# logic-noise-filters-and-drums.net
KiCad netlist of a schematic drawn in EAGLE
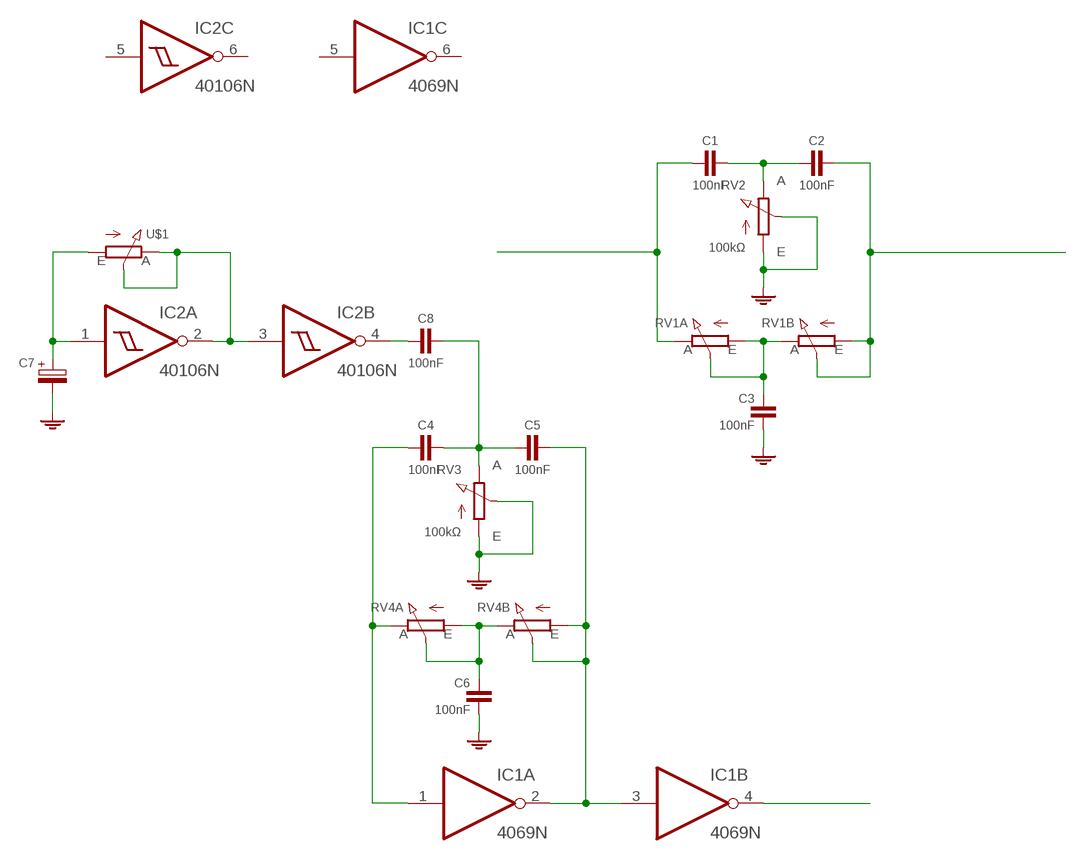
[diagram p0: schematic, sheet 1]

(export (version "E")
  (design (tool "Eeschema 10.0.6"))
  (components
    (comp (ref "C1")
      (value "100nF")
      (footprint "eagle-import:C075-020X044")
      (libsource (lib "eagle-import") (part "C-H075-020X044"))
    )
    (comp (ref "C2")
      (value "100nF")
      (footprint "eagle-import:C075-020X044")
      (libsource (lib "eagle-import") (part "C-H075-020X044"))
    )
    (comp (ref "C3")
      (value "100nF")
      (footprint "eagle-import:C075-020X044")
      (libsource (lib "eagle-import") (part "C075-020X044"))
    )
    (comp (ref "C4")
      (value "100nF")
      (footprint "eagle-import:C075-020X044")
      (libsource (lib "eagle-import") (part "C-H075-020X044"))
    )
    (comp (ref "C5")
      (value "100nF")
      (footprint "eagle-import:C075-020X044")
      (libsource (lib "eagle-import") (part "C-H075-020X044"))
    )
    (comp (ref "C6")
      (value "100nF")
      (footprint "eagle-import:C075-020X044")
      (libsource (lib "eagle-import") (part "C075-020X044"))
    )
    (comp (ref "C7")
      (value "CPOLE2,5-5/V")
      (footprint "eagle-import:E2,5-5_V")
      (libsource (lib "eagle-import") (part "CPOLE2,5-5/V"))
    )
    (comp (ref "C8")
      (value "100nF")
      (footprint "eagle-import:C075-020X044")
      (libsource (lib "eagle-import") (part "C-H075-020X044"))
    )
    (comp (ref "IC1")
      (value "4069N")
      (footprint "eagle-import:DIL14")
      (libsource (lib "eagle-import") (part "4069N"))
    )
    (comp (ref "IC2")
      (value "40106N")
      (footprint "eagle-import:DIL14")
      (libsource (lib "eagle-import") (part "40106N"))
    )
    (comp (ref "RV1")
      (value "POT-STEREO")
      (footprint "eagle-import:POT-STEREO-2X3")
      (libsource (lib "eagle-import") (part "POT-STEREO"))
    )
    (comp (ref "RV2")
      (value "100kΩ")
      (footprint "eagle-import:POT")
      (libsource (lib "eagle-import") (part "POT"))
    )
    (comp (ref "RV3")
      (value "100kΩ")
      (footprint "eagle-import:POT")
      (libsource (lib "eagle-import") (part "POT"))
    )
    (comp (ref "RV4")
      (value "POT-STEREO")
      (footprint "eagle-import:POT-STEREO-2X3")
      (libsource (lib "eagle-import") (part "POT-STEREO"))
    )
    (comp (ref "U$1")
      (value "POT-H")
      (footprint "eagle-import:POT")
      (libsource (lib "eagle-import") (part "POT-H"))
    )
  )
  (nets
    (net (code "1") (name "GND") (class "Default")
      (node (ref "C3") (pin "2") (pinfunction "2_2") (pintype "passive"))
      (node (ref "C6") (pin "2") (pinfunction "2_2") (pintype "passive"))
      (node (ref "C7") (pin "-") (pinfunction "-_-") (pintype "passive"))
      (node (ref "RV2") (pin "A") (pinfunction "A_A") (pintype "passive"))
      (node (ref "RV2") (pin "S") (pinfunction "S_S") (pintype "passive"))
      (node (ref "RV3") (pin "A") (pinfunction "A_A") (pintype "passive"))
      (node (ref "RV3") (pin "S") (pinfunction "S_S") (pintype "passive"))
    )
    (net (code "2") (name "Net-(C1-Pad2)") (class "Default")
      (node (ref "C1") (pin "2") (pinfunction "2_2") (pintype "passive"))
      (node (ref "C2") (pin "1") (pinfunction "1_1") (pintype "passive"))
      (node (ref "RV2") (pin "E") (pinfunction "E_E") (pintype "passive"))
    )
    (net (code "3") (name "Net-(C4-Pad2)") (class "Default")
      (node (ref "C4") (pin "2") (pinfunction "2_2") (pintype "passive"))
      (node (ref "C5") (pin "1") (pinfunction "1_1") (pintype "passive"))
      (node (ref "C8") (pin "2") (pinfunction "2_2") (pintype "passive"))
      (node (ref "RV3") (pin "E") (pinfunction "E_E") (pintype "passive"))
    )
    (net (code "4") (name "Net-(IC1A-I)") (class "Default")
      (node (ref "C4") (pin "1") (pinfunction "1_1") (pintype "passive"))
      (node (ref "IC1") (pin "1") (pinfunction "I_1") (pintype "input"))
      (node (ref "RV4") (pin "1-E") (pinfunction "E_1-E") (pintype "passive"))
    )
    (net (code "5") (name "Net-(IC1A-O)") (class "Default")
      (node (ref "C5") (pin "2") (pinfunction "2_2") (pintype "passive"))
      (node (ref "IC1") (pin "2") (pinfunction "O_2") (pintype "output"))
      (node (ref "IC1") (pin "3") (pinfunction "I_3") (pintype "input"))
      (node (ref "RV4") (pin "2-A") (pinfunction "A_2-A") (pintype "passive"))
      (node (ref "RV4") (pin "2-S") (pinfunction "S_2-S") (pintype "passive"))
    )
    (net (code "6") (name "Net-(IC2A-I)") (class "Default")
      (node (ref "C7") (pin "+") (pinfunction "+_+") (pintype "passive"))
      (node (ref "IC2") (pin "1") (pinfunction "I_1") (pintype "input"))
      (node (ref "U$1") (pin "A") (pinfunction "A_A") (pintype "passive"))
    )
    (net (code "7") (name "Net-(IC2A-O)") (class "Default")
      (node (ref "IC2") (pin "2") (pinfunction "O_2") (pintype "output"))
      (node (ref "IC2") (pin "3") (pinfunction "I_3") (pintype "input"))
      (node (ref "U$1") (pin "E") (pinfunction "E_E") (pintype "passive"))
      (node (ref "U$1") (pin "S") (pinfunction "S_S") (pintype "passive"))
    )
    (net (code "8") (name "Net-(IC2B-O)") (class "Default")
      (node (ref "C8") (pin "1") (pinfunction "1_1") (pintype "passive"))
      (node (ref "IC2") (pin "4") (pinfunction "O_4") (pintype "output"))
    )
    (net (code "9") (name "Net-(RV1A-A)") (class "Default")
      (node (ref "C3") (pin "1") (pinfunction "1_1") (pintype "passive"))
      (node (ref "RV1") (pin "1-A") (pinfunction "A_1-A") (pintype "passive"))
      (node (ref "RV1") (pin "1-S") (pinfunction "S_1-S") (pintype "passive"))
      (node (ref "RV1") (pin "2-E") (pinfunction "E_2-E") (pintype "passive"))
    )
    (net (code "10") (name "Net-(RV1A-E)") (class "Default")
      (node (ref "C1") (pin "1") (pinfunction "1_1") (pintype "passive"))
      (node (ref "RV1") (pin "1-E") (pinfunction "E_1-E") (pintype "passive"))
    )
    (net (code "11") (name "Net-(RV1B-A)") (class "Default")
      (node (ref "C2") (pin "2") (pinfunction "2_2") (pintype "passive"))
      (node (ref "RV1") (pin "2-A") (pinfunction "A_2-A") (pintype "passive"))
      (node (ref "RV1") (pin "2-S") (pinfunction "S_2-S") (pintype "passive"))
    )
    (net (code "12") (name "Net-(RV4A-A)") (class "Default")
      (node (ref "C6") (pin "1") (pinfunction "1_1") (pintype "passive"))
      (node (ref "RV4") (pin "1-A") (pinfunction "A_1-A") (pintype "passive"))
      (node (ref "RV4") (pin "1-S") (pinfunction "S_1-S") (pintype "passive"))
      (node (ref "RV4") (pin "2-E") (pinfunction "E_2-E") (pintype "passive"))
    )
    (net (code "13") (name "unconnected-(IC1B-O-Pad4)") (class "Default")
      (node (ref "IC1") (pin "4") (pinfunction "O_4") (pintype "output"))
    )
    (net (code "14") (name "unconnected-(IC1C-I-Pad5)") (class "Default")
      (node (ref "IC1") (pin "5") (pinfunction "I_5") (pintype "input"))
    )
    (net (code "15") (name "unconnected-(IC1C-O-Pad6)") (class "Default")
      (node (ref "IC1") (pin "6") (pinfunction "O_6") (pintype "output"))
    )
    (net (code "16") (name "unconnected-(IC2C-I-Pad5)") (class "Default")
      (node (ref "IC2") (pin "5") (pinfunction "I_5") (pintype "input"))
    )
    (net (code "17") (name "unconnected-(IC2C-O-Pad6)") (class "Default")
      (node (ref "IC2") (pin "6") (pinfunction "O_6") (pintype "output"))
    )
  )
)
